# Bv_Remote.net
KiCad netlist of a schematic drawn in EAGLE
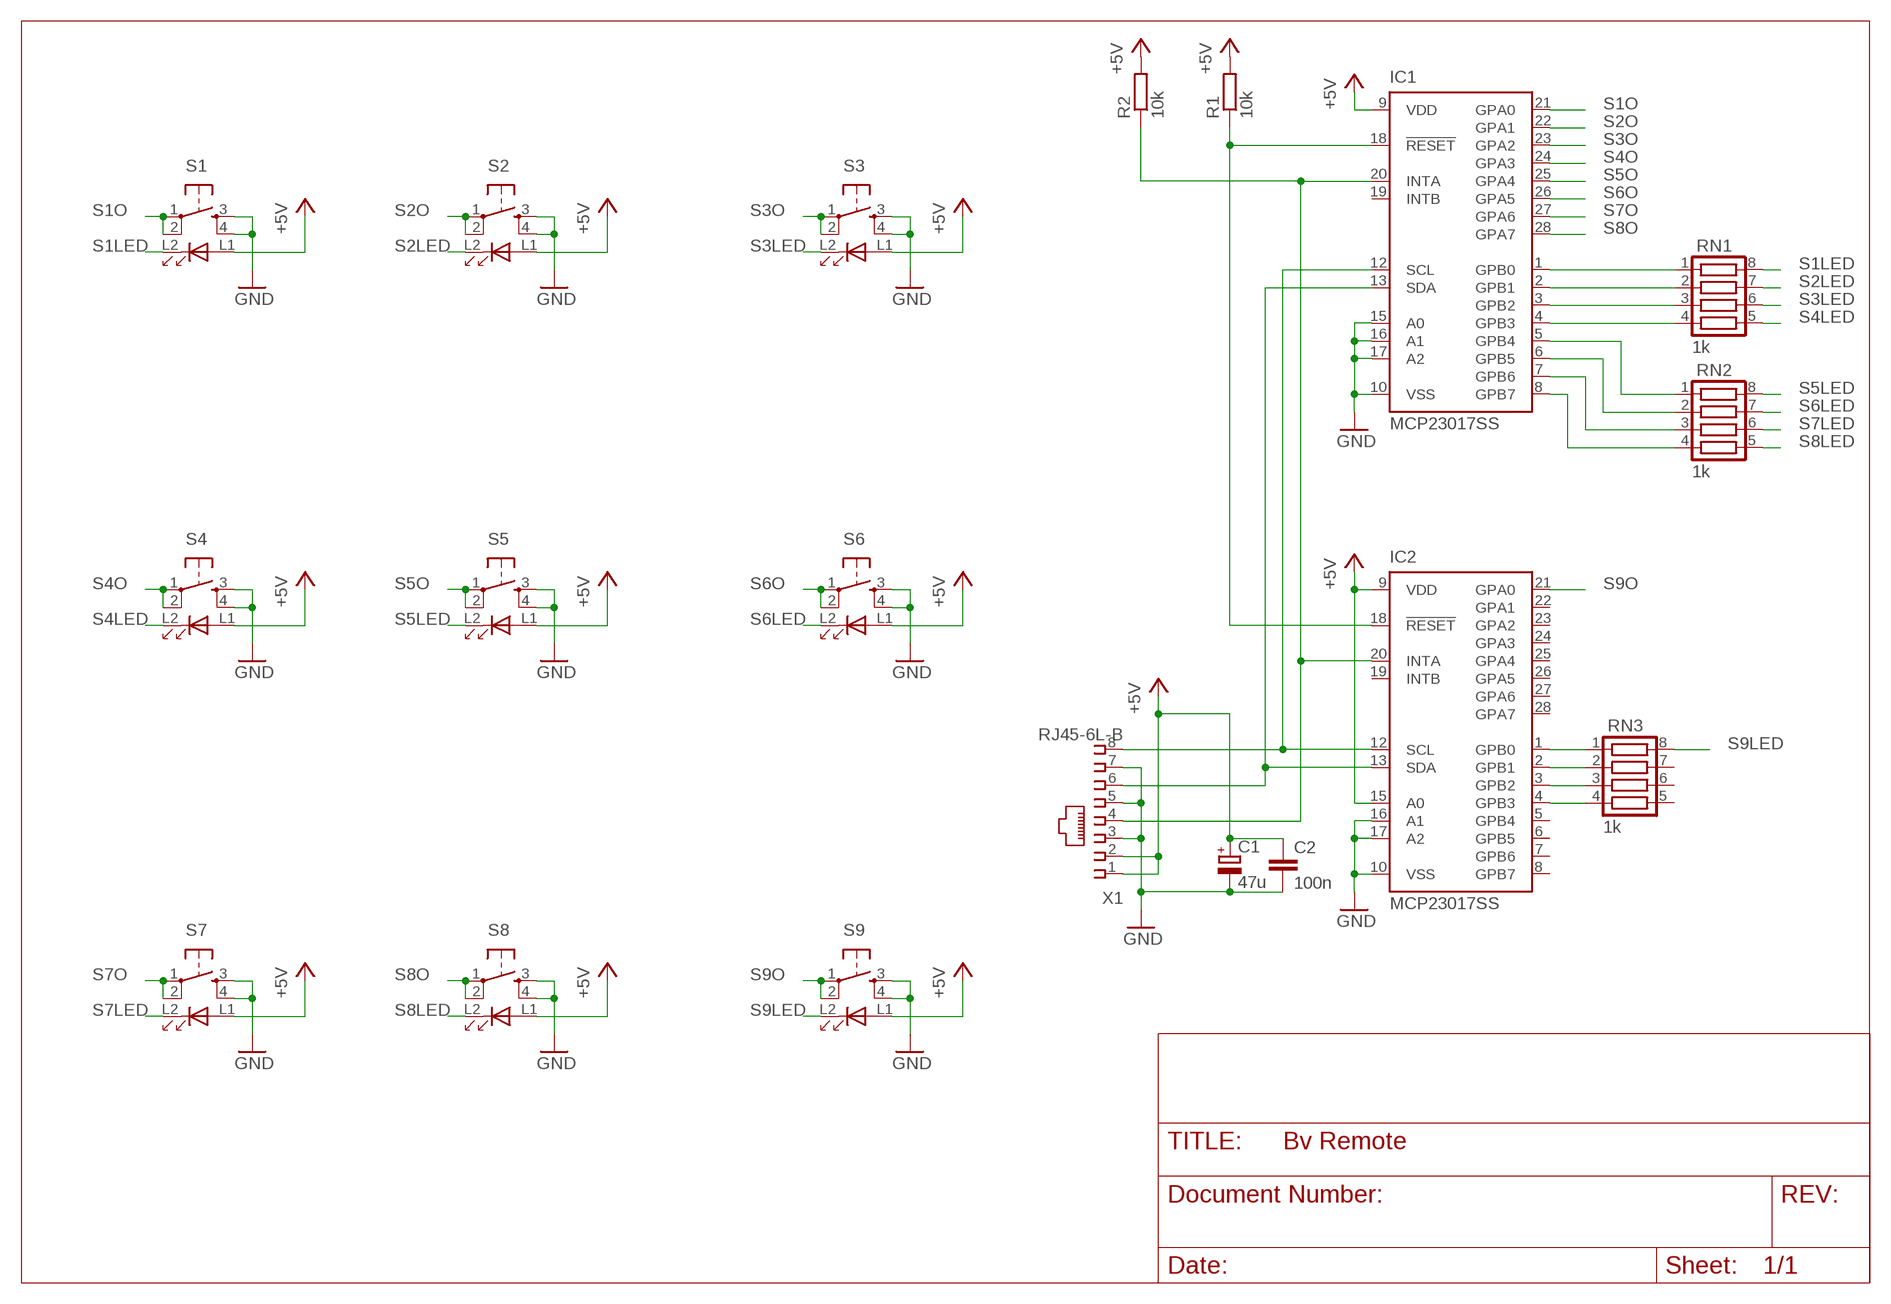
[diagram p0: schematic, sheet 1]

(export (version "E")
  (design (tool "Eeschema 10.0.6"))
  (components
    (comp (ref "C1")
      (value "47u")
      (footprint "eagle-import:153CLV-1010")
      (libsource (lib "eagle-import") (part "CPOL-EU153CLV-1010"))
    )
    (comp (ref "C2")
      (value "100n")
      (footprint "eagle-import:C1206")
      (libsource (lib "eagle-import") (part "C-EUC1206"))
    )
    (comp (ref "IC1")
      (value "MCP23017SS")
      (footprint "eagle-import:SSOP28")
      (fields (field (name "MF") "MICROCHIP") (field (name "MPN") "MCP23017-E/SS"))
      (libsource (lib "eagle-import") (part "MCP23017SS"))
    )
    (comp (ref "IC2")
      (value "MCP23017SS")
      (footprint "eagle-import:SSOP28")
      (fields (field (name "MF") "MICROCHIP") (field (name "MPN") "MCP23017-E/SS"))
      (libsource (lib "eagle-import") (part "MCP23017SS"))
    )
    (comp (ref "R1")
      (value "10k")
      (footprint "eagle-import:R1206")
      (libsource (lib "eagle-import") (part "R-EU_R1206"))
    )
    (comp (ref "R2")
      (value "10k")
      (footprint "eagle-import:R1206")
      (libsource (lib "eagle-import") (part "R-EU_R1206"))
    )
    (comp (ref "RN1")
      (value "1k")
      (footprint "eagle-import:CTS742C083")
      (libsource (lib "eagle-import") (part "CTS742C083"))
    )
    (comp (ref "RN2")
      (value "1k")
      (footprint "eagle-import:CTS742C083")
      (libsource (lib "eagle-import") (part "CTS742C083"))
    )
    (comp (ref "RN3")
      (value "1k")
      (footprint "eagle-import:CTS742C083")
      (libsource (lib "eagle-import") (part "CTS742C083"))
    )
    (comp (ref "S1")
      (value "TS_HIGHLY_LED")
      (footprint "eagle-import:PB614_TACT")
      (libsource (lib "eagle-import") (part "TS_HIGHLY_LED"))
    )
    (comp (ref "S2")
      (value "TS_HIGHLY_LED")
      (footprint "eagle-import:PB614_TACT")
      (libsource (lib "eagle-import") (part "TS_HIGHLY_LED"))
    )
    (comp (ref "S3")
      (value "TS_HIGHLY_LED")
      (footprint "eagle-import:PB614_TACT")
      (libsource (lib "eagle-import") (part "TS_HIGHLY_LED"))
    )
    (comp (ref "S4")
      (value "TS_HIGHLY_LED")
      (footprint "eagle-import:PB614_TACT")
      (libsource (lib "eagle-import") (part "TS_HIGHLY_LED"))
    )
    (comp (ref "S5")
      (value "TS_HIGHLY_LED")
      (footprint "eagle-import:PB614_TACT")
      (libsource (lib "eagle-import") (part "TS_HIGHLY_LED"))
    )
    (comp (ref "S6")
      (value "TS_HIGHLY_LED")
      (footprint "eagle-import:PB614_TACT")
      (libsource (lib "eagle-import") (part "TS_HIGHLY_LED"))
    )
    (comp (ref "S7")
      (value "TS_HIGHLY_LED")
      (footprint "eagle-import:PB614_TACT")
      (libsource (lib "eagle-import") (part "TS_HIGHLY_LED"))
    )
    (comp (ref "S8")
      (value "TS_HIGHLY_LED")
      (footprint "eagle-import:PB614_TACT")
      (libsource (lib "eagle-import") (part "TS_HIGHLY_LED"))
    )
    (comp (ref "S9")
      (value "TS_HIGHLY_LED")
      (footprint "eagle-import:PB614_TACT")
      (libsource (lib "eagle-import") (part "TS_HIGHLY_LED"))
    )
    (comp (ref "X1")
      (value "RJ45-6L-B")
      (footprint "eagle-import:RJ45-NO-SHIELD")
      (libsource (lib "eagle-import") (part "RJ45-6L-B"))
    )
  )
  (nets
    (net (code "1") (name "+5V") (class "Default")
      (node (ref "C1") (pin "+") (pinfunction "+_+") (pintype "passive"))
      (node (ref "C2") (pin "1") (pinfunction "1_1") (pintype "passive"))
      (node (ref "IC1") (pin "9") (pinfunction "VDD_9") (pintype "power_in"))
      (node (ref "IC2") (pin "15") (pinfunction "A0_15") (pintype "input"))
      (node (ref "IC2") (pin "9") (pinfunction "VDD_9") (pintype "power_in"))
      (node (ref "R1") (pin "2") (pinfunction "2_2") (pintype "passive"))
      (node (ref "R2") (pin "2") (pinfunction "2_2") (pintype "passive"))
      (node (ref "S1") (pin "L1") (pinfunction "A_L1") (pintype "passive"))
      (node (ref "S2") (pin "L1") (pinfunction "A_L1") (pintype "passive"))
      (node (ref "S3") (pin "L1") (pinfunction "A_L1") (pintype "passive"))
      (node (ref "S4") (pin "L1") (pinfunction "A_L1") (pintype "passive"))
      (node (ref "S5") (pin "L1") (pinfunction "A_L1") (pintype "passive"))
      (node (ref "S6") (pin "L1") (pinfunction "A_L1") (pintype "passive"))
      (node (ref "S7") (pin "L1") (pinfunction "A_L1") (pintype "passive"))
      (node (ref "S8") (pin "L1") (pinfunction "A_L1") (pintype "passive"))
      (node (ref "S9") (pin "L1") (pinfunction "A_L1") (pintype "passive"))
      (node (ref "X1") (pin "1") (pinfunction "1_1") (pintype "passive"))
      (node (ref "X1") (pin "2") (pinfunction "2_2") (pintype "passive"))
    )
    (net (code "2") (name "/S1LED") (class "Default")
      (node (ref "RN1") (pin "8") (pinfunction "8_8") (pintype "passive"))
      (node (ref "S1") (pin "L2") (pinfunction "C_L2") (pintype "passive"))
    )
    (net (code "3") (name "/S1O") (class "Default")
      (node (ref "IC1") (pin "21") (pinfunction "GPA0_21") (pintype "bidirectional"))
      (node (ref "S1") (pin "1") (pinfunction "P_1") (pintype "passive"))
      (node (ref "S1") (pin "2") (pinfunction "P1_2") (pintype "passive"))
    )
    (net (code "4") (name "/S2LED") (class "Default")
      (node (ref "RN1") (pin "7") (pinfunction "7_7") (pintype "passive"))
      (node (ref "S2") (pin "L2") (pinfunction "C_L2") (pintype "passive"))
    )
    (net (code "5") (name "/S2O") (class "Default")
      (node (ref "IC1") (pin "22") (pinfunction "GPA1_22") (pintype "bidirectional"))
      (node (ref "S2") (pin "1") (pinfunction "P_1") (pintype "passive"))
      (node (ref "S2") (pin "2") (pinfunction "P1_2") (pintype "passive"))
    )
    (net (code "6") (name "/S3LED") (class "Default")
      (node (ref "RN1") (pin "6") (pinfunction "6_6") (pintype "passive"))
      (node (ref "S3") (pin "L2") (pinfunction "C_L2") (pintype "passive"))
    )
    (net (code "7") (name "/S3O") (class "Default")
      (node (ref "IC1") (pin "23") (pinfunction "GPA2_23") (pintype "bidirectional"))
      (node (ref "S3") (pin "1") (pinfunction "P_1") (pintype "passive"))
      (node (ref "S3") (pin "2") (pinfunction "P1_2") (pintype "passive"))
    )
    (net (code "8") (name "/S4LED") (class "Default")
      (node (ref "RN1") (pin "5") (pinfunction "5_5") (pintype "passive"))
      (node (ref "S4") (pin "L2") (pinfunction "C_L2") (pintype "passive"))
    )
    (net (code "9") (name "/S4O") (class "Default")
      (node (ref "IC1") (pin "24") (pinfunction "GPA3_24") (pintype "bidirectional"))
      (node (ref "S4") (pin "1") (pinfunction "P_1") (pintype "passive"))
      (node (ref "S4") (pin "2") (pinfunction "P1_2") (pintype "passive"))
    )
    (net (code "10") (name "/S5LED") (class "Default")
      (node (ref "RN2") (pin "8") (pinfunction "8_8") (pintype "passive"))
      (node (ref "S5") (pin "L2") (pinfunction "C_L2") (pintype "passive"))
    )
    (net (code "11") (name "/S5O") (class "Default")
      (node (ref "IC1") (pin "25") (pinfunction "GPA4_25") (pintype "bidirectional"))
      (node (ref "S5") (pin "1") (pinfunction "P_1") (pintype "passive"))
      (node (ref "S5") (pin "2") (pinfunction "P1_2") (pintype "passive"))
    )
    (net (code "12") (name "/S6LED") (class "Default")
      (node (ref "RN2") (pin "7") (pinfunction "7_7") (pintype "passive"))
      (node (ref "S6") (pin "L2") (pinfunction "C_L2") (pintype "passive"))
    )
    (net (code "13") (name "/S6O") (class "Default")
      (node (ref "IC1") (pin "26") (pinfunction "GPA5_26") (pintype "bidirectional"))
      (node (ref "S6") (pin "1") (pinfunction "P_1") (pintype "passive"))
      (node (ref "S6") (pin "2") (pinfunction "P1_2") (pintype "passive"))
    )
    (net (code "14") (name "/S7LED") (class "Default")
      (node (ref "RN2") (pin "6") (pinfunction "6_6") (pintype "passive"))
      (node (ref "S7") (pin "L2") (pinfunction "C_L2") (pintype "passive"))
    )
    (net (code "15") (name "/S7O") (class "Default")
      (node (ref "IC1") (pin "27") (pinfunction "GPA6_27") (pintype "bidirectional"))
      (node (ref "S7") (pin "1") (pinfunction "P_1") (pintype "passive"))
      (node (ref "S7") (pin "2") (pinfunction "P1_2") (pintype "passive"))
    )
    (net (code "16") (name "/S8LED") (class "Default")
      (node (ref "RN2") (pin "5") (pinfunction "5_5") (pintype "passive"))
      (node (ref "S8") (pin "L2") (pinfunction "C_L2") (pintype "passive"))
    )
    (net (code "17") (name "/S8O") (class "Default")
      (node (ref "IC1") (pin "28") (pinfunction "GPA7_28") (pintype "bidirectional"))
      (node (ref "S8") (pin "1") (pinfunction "P_1") (pintype "passive"))
      (node (ref "S8") (pin "2") (pinfunction "P1_2") (pintype "passive"))
    )
    (net (code "18") (name "/S9LED") (class "Default")
      (node (ref "RN3") (pin "8") (pinfunction "8_8") (pintype "passive"))
      (node (ref "S9") (pin "L2") (pinfunction "C_L2") (pintype "passive"))
    )
    (net (code "19") (name "/S9O") (class "Default")
      (node (ref "IC2") (pin "21") (pinfunction "GPA0_21") (pintype "bidirectional"))
      (node (ref "S9") (pin "1") (pinfunction "P_1") (pintype "passive"))
      (node (ref "S9") (pin "2") (pinfunction "P1_2") (pintype "passive"))
    )
    (net (code "20") (name "GND") (class "Default")
      (node (ref "C1") (pin "-") (pinfunction "-_-") (pintype "passive"))
      (node (ref "C2") (pin "2") (pinfunction "2_2") (pintype "passive"))
      (node (ref "IC1") (pin "10") (pinfunction "VSS_10") (pintype "power_in"))
      (node (ref "IC1") (pin "15") (pinfunction "A0_15") (pintype "input"))
      (node (ref "IC1") (pin "16") (pinfunction "A1_16") (pintype "input"))
      (node (ref "IC1") (pin "17") (pinfunction "A2_17") (pintype "input"))
      (node (ref "IC2") (pin "10") (pinfunction "VSS_10") (pintype "power_in"))
      (node (ref "IC2") (pin "16") (pinfunction "A1_16") (pintype "input"))
      (node (ref "IC2") (pin "17") (pinfunction "A2_17") (pintype "input"))
      (node (ref "S1") (pin "3") (pinfunction "S_3") (pintype "passive"))
      (node (ref "S1") (pin "4") (pinfunction "S1_4") (pintype "passive"))
      (node (ref "S2") (pin "3") (pinfunction "S_3") (pintype "passive"))
      (node (ref "S2") (pin "4") (pinfunction "S1_4") (pintype "passive"))
      (node (ref "S3") (pin "3") (pinfunction "S_3") (pintype "passive"))
      (node (ref "S3") (pin "4") (pinfunction "S1_4") (pintype "passive"))
      (node (ref "S4") (pin "3") (pinfunction "S_3") (pintype "passive"))
      (node (ref "S4") (pin "4") (pinfunction "S1_4") (pintype "passive"))
      (node (ref "S5") (pin "3") (pinfunction "S_3") (pintype "passive"))
      (node (ref "S5") (pin "4") (pinfunction "S1_4") (pintype "passive"))
      (node (ref "S6") (pin "3") (pinfunction "S_3") (pintype "passive"))
      (node (ref "S6") (pin "4") (pinfunction "S1_4") (pintype "passive"))
      (node (ref "S7") (pin "3") (pinfunction "S_3") (pintype "passive"))
      (node (ref "S7") (pin "4") (pinfunction "S1_4") (pintype "passive"))
      (node (ref "S8") (pin "3") (pinfunction "S_3") (pintype "passive"))
      (node (ref "S8") (pin "4") (pinfunction "S1_4") (pintype "passive"))
      (node (ref "S9") (pin "3") (pinfunction "S_3") (pintype "passive"))
      (node (ref "S9") (pin "4") (pinfunction "S1_4") (pintype "passive"))
      (node (ref "X1") (pin "3") (pinfunction "3_3") (pintype "passive"))
      (node (ref "X1") (pin "5") (pinfunction "5_5") (pintype "passive"))
      (node (ref "X1") (pin "7") (pinfunction "7_7") (pintype "passive"))
    )
    (net (code "21") (name "Net-(IC1-GPB0)") (class "Default")
      (node (ref "IC1") (pin "1") (pinfunction "GPB0_1") (pintype "bidirectional"))
      (node (ref "RN1") (pin "1") (pinfunction "1_1") (pintype "passive"))
    )
    (net (code "22") (name "Net-(IC1-GPB1)") (class "Default")
      (node (ref "IC1") (pin "2") (pinfunction "GPB1_2") (pintype "bidirectional"))
      (node (ref "RN1") (pin "2") (pinfunction "2_2") (pintype "passive"))
    )
    (net (code "23") (name "Net-(IC1-GPB2)") (class "Default")
      (node (ref "IC1") (pin "3") (pinfunction "GPB2_3") (pintype "bidirectional"))
      (node (ref "RN1") (pin "3") (pinfunction "3_3") (pintype "passive"))
    )
    (net (code "24") (name "Net-(IC1-GPB3)") (class "Default")
      (node (ref "IC1") (pin "4") (pinfunction "GPB3_4") (pintype "bidirectional"))
      (node (ref "RN1") (pin "4") (pinfunction "4_4") (pintype "passive"))
    )
    (net (code "25") (name "Net-(IC1-GPB4)") (class "Default")
      (node (ref "IC1") (pin "5") (pinfunction "GPB4_5") (pintype "bidirectional"))
      (node (ref "RN2") (pin "1") (pinfunction "1_1") (pintype "passive"))
    )
    (net (code "26") (name "Net-(IC1-GPB5)") (class "Default")
      (node (ref "IC1") (pin "6") (pinfunction "GPB5_6") (pintype "bidirectional"))
      (node (ref "RN2") (pin "2") (pinfunction "2_2") (pintype "passive"))
    )
    (net (code "27") (name "Net-(IC1-GPB6)") (class "Default")
      (node (ref "IC1") (pin "7") (pinfunction "GPB6_7") (pintype "bidirectional"))
      (node (ref "RN2") (pin "3") (pinfunction "3_3") (pintype "passive"))
    )
    (net (code "28") (name "Net-(IC1-GPB7)") (class "Default")
      (node (ref "IC1") (pin "8") (pinfunction "GPB7_8") (pintype "bidirectional"))
      (node (ref "RN2") (pin "4") (pinfunction "4_4") (pintype "passive"))
    )
    (net (code "29") (name "Net-(IC1-INTA)") (class "Default")
      (node (ref "IC1") (pin "20") (pinfunction "INTA_20") (pintype "output"))
      (node (ref "IC2") (pin "20") (pinfunction "INTA_20") (pintype "output"))
      (node (ref "R2") (pin "1") (pinfunction "1_1") (pintype "passive"))
      (node (ref "X1") (pin "4") (pinfunction "4_4") (pintype "passive"))
    )
    (net (code "30") (name "Net-(IC1-SCL)") (class "Default")
      (node (ref "IC1") (pin "12") (pinfunction "SCL_12") (pintype "input"))
      (node (ref "IC2") (pin "12") (pinfunction "SCL_12") (pintype "input"))
      (node (ref "X1") (pin "8") (pinfunction "8_8") (pintype "passive"))
    )
    (net (code "31") (name "Net-(IC1-SDA)") (class "Default")
      (node (ref "IC1") (pin "13") (pinfunction "SDA_13") (pintype "bidirectional"))
      (node (ref "IC2") (pin "13") (pinfunction "SDA_13") (pintype "bidirectional"))
      (node (ref "X1") (pin "6") (pinfunction "6_6") (pintype "passive"))
    )
    (net (code "32") (name "Net-(IC1-~{RESET})") (class "Default")
      (node (ref "IC1") (pin "18") (pinfunction "~{RESET}_18") (pintype "input"))
      (node (ref "IC2") (pin "18") (pinfunction "~{RESET}_18") (pintype "input"))
      (node (ref "R1") (pin "1") (pinfunction "1_1") (pintype "passive"))
    )
    (net (code "33") (name "Net-(IC2-GPB0)") (class "Default")
      (node (ref "IC2") (pin "1") (pinfunction "GPB0_1") (pintype "bidirectional"))
      (node (ref "RN3") (pin "1") (pinfunction "1_1") (pintype "passive"))
    )
    (net (code "34") (name "Net-(IC2-GPB1)") (class "Default")
      (node (ref "IC2") (pin "2") (pinfunction "GPB1_2") (pintype "bidirectional"))
      (node (ref "RN3") (pin "2") (pinfunction "2_2") (pintype "passive"))
    )
    (net (code "35") (name "Net-(IC2-GPB2)") (class "Default")
      (node (ref "IC2") (pin "3") (pinfunction "GPB2_3") (pintype "bidirectional"))
      (node (ref "RN3") (pin "3") (pinfunction "3_3") (pintype "passive"))
    )
    (net (code "36") (name "Net-(IC2-GPB3)") (class "Default")
      (node (ref "IC2") (pin "4") (pinfunction "GPB3_4") (pintype "bidirectional"))
      (node (ref "RN3") (pin "4") (pinfunction "4_4") (pintype "passive"))
    )
    (net (code "37") (name "unconnected-(IC1-INTB-Pad19)") (class "Default")
      (node (ref "IC1") (pin "19") (pinfunction "INTB_19") (pintype "output"))
    )
    (net (code "38") (name "unconnected-(IC2-GPA1-Pad22)") (class "Default")
      (node (ref "IC2") (pin "22") (pinfunction "GPA1_22") (pintype "bidirectional"))
    )
    (net (code "39") (name "unconnected-(IC2-GPA2-Pad23)") (class "Default")
      (node (ref "IC2") (pin "23") (pinfunction "GPA2_23") (pintype "bidirectional"))
    )
    (net (code "40") (name "unconnected-(IC2-GPA3-Pad24)") (class "Default")
      (node (ref "IC2") (pin "24") (pinfunction "GPA3_24") (pintype "bidirectional"))
    )
    (net (code "41") (name "unconnected-(IC2-GPA4-Pad25)") (class "Default")
      (node (ref "IC2") (pin "25") (pinfunction "GPA4_25") (pintype "bidirectional"))
    )
    (net (code "42") (name "unconnected-(IC2-GPA5-Pad26)") (class "Default")
      (node (ref "IC2") (pin "26") (pinfunction "GPA5_26") (pintype "bidirectional"))
    )
    (net (code "43") (name "unconnected-(IC2-GPA6-Pad27)") (class "Default")
      (node (ref "IC2") (pin "27") (pinfunction "GPA6_27") (pintype "bidirectional"))
    )
    (net (code "44") (name "unconnected-(IC2-GPA7-Pad28)") (class "Default")
      (node (ref "IC2") (pin "28") (pinfunction "GPA7_28") (pintype "bidirectional"))
    )
    (net (code "45") (name "unconnected-(IC2-GPB4-Pad5)") (class "Default")
      (node (ref "IC2") (pin "5") (pinfunction "GPB4_5") (pintype "bidirectional"))
    )
    (net (code "46") (name "unconnected-(IC2-GPB5-Pad6)") (class "Default")
      (node (ref "IC2") (pin "6") (pinfunction "GPB5_6") (pintype "bidirectional"))
    )
    (net (code "47") (name "unconnected-(IC2-GPB6-Pad7)") (class "Default")
      (node (ref "IC2") (pin "7") (pinfunction "GPB6_7") (pintype "bidirectional"))
    )
    (net (code "48") (name "unconnected-(IC2-GPB7-Pad8)") (class "Default")
      (node (ref "IC2") (pin "8") (pinfunction "GPB7_8") (pintype "bidirectional"))
    )
    (net (code "49") (name "unconnected-(IC2-INTB-Pad19)") (class "Default")
      (node (ref "IC2") (pin "19") (pinfunction "INTB_19") (pintype "output"))
    )
    (net (code "50") (name "unconnected-(RN3-Pad5)") (class "Default")
      (node (ref "RN3") (pin "5") (pinfunction "5_5") (pintype "passive"))
    )
    (net (code "51") (name "unconnected-(RN3-Pad6)") (class "Default")
      (node (ref "RN3") (pin "6") (pinfunction "6_6") (pintype "passive"))
    )
    (net (code "52") (name "unconnected-(RN3-Pad7)") (class "Default")
      (node (ref "RN3") (pin "7") (pinfunction "7_7") (pintype "passive"))
    )
  )
)
